# ESP32-ADC.net
KiCad netlist of a schematic drawn in EAGLE
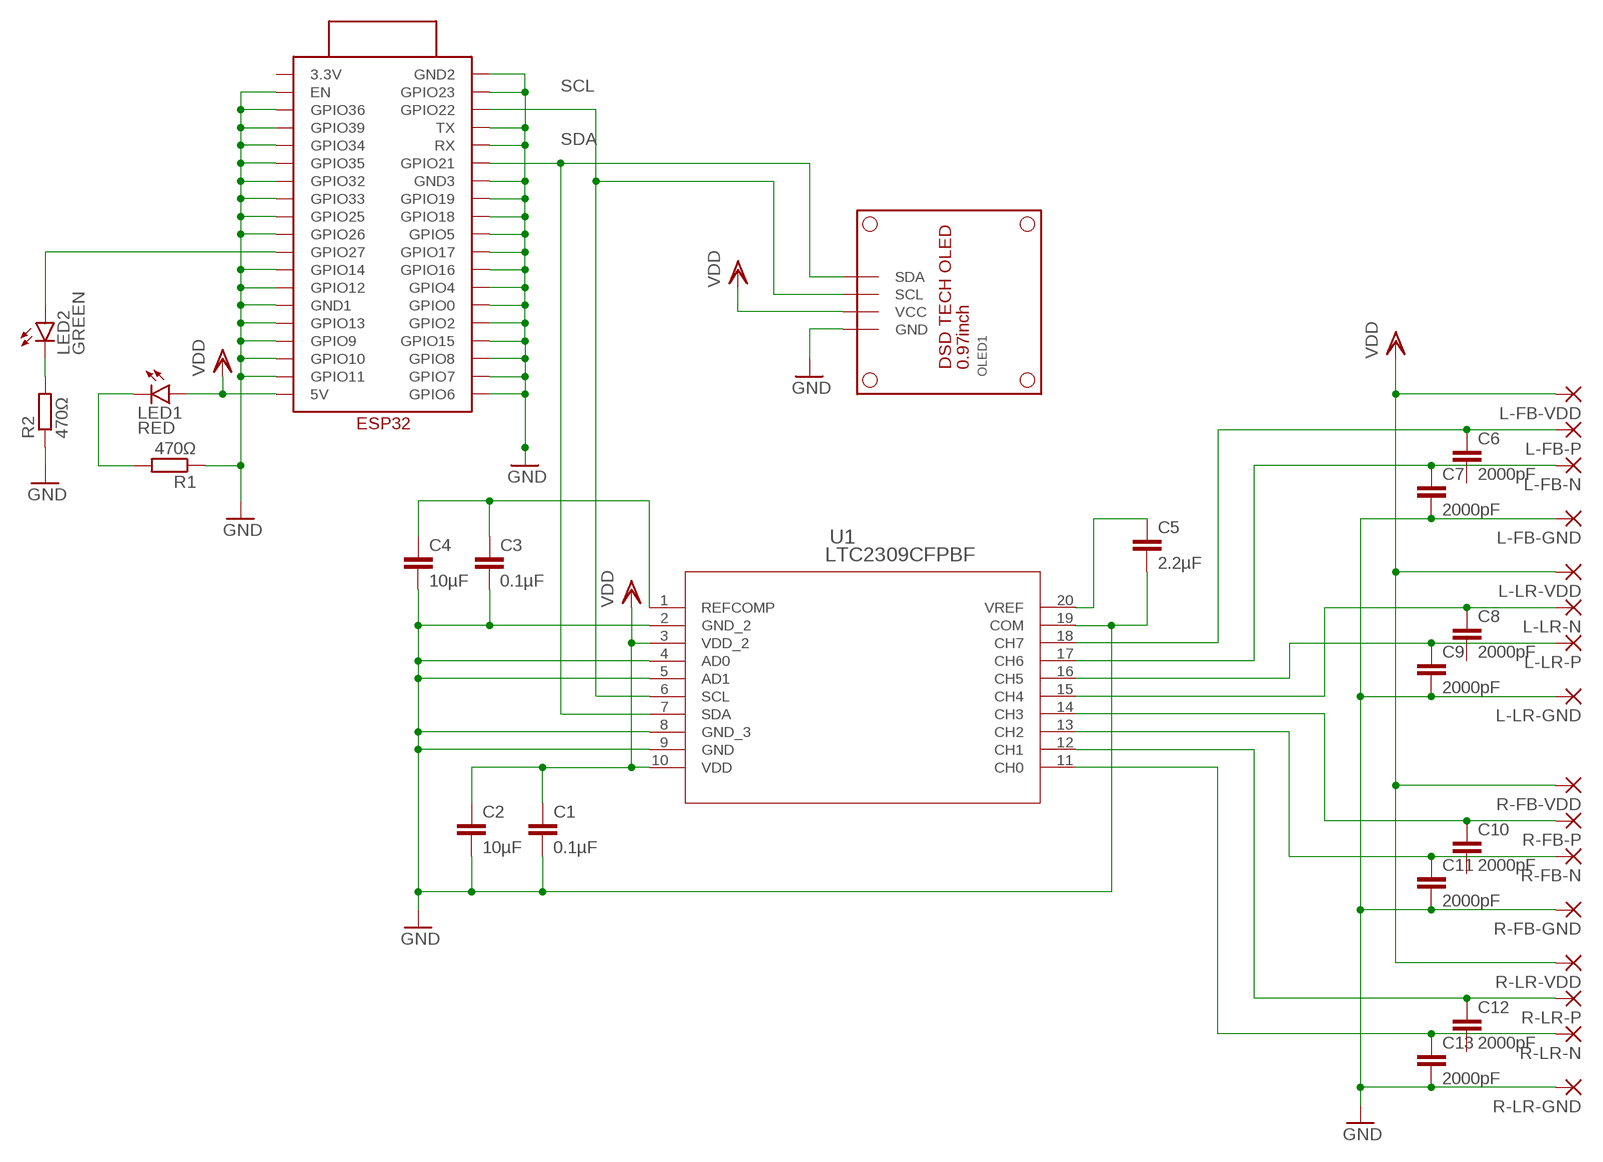
[diagram p0: schematic, sheet 1]

(export (version "E")
  (design (tool "Eeschema 10.0.6"))
  (components
    (comp (ref "C1")
      (value "0.1µF")
      (footprint "eagle-import:C3216")
      (libsource (lib "eagle-import") (part "C-EUC3216"))
    )
    (comp (ref "C2")
      (value "10µF")
      (footprint "eagle-import:C3216")
      (libsource (lib "eagle-import") (part "C-EUC3216"))
    )
    (comp (ref "C3")
      (value "0.1µF")
      (footprint "eagle-import:C3216")
      (libsource (lib "eagle-import") (part "C-EUC3216"))
    )
    (comp (ref "C4")
      (value "10µF")
      (footprint "eagle-import:C3216")
      (libsource (lib "eagle-import") (part "C-EUC3216"))
    )
    (comp (ref "C5")
      (value "2.2µF")
      (footprint "eagle-import:C3216")
      (libsource (lib "eagle-import") (part "C-EUC3216"))
    )
    (comp (ref "C6")
      (value "2000pF")
      (footprint "eagle-import:C3216")
      (libsource (lib "eagle-import") (part "C-EUC3216"))
    )
    (comp (ref "C7")
      (value "2000pF")
      (footprint "eagle-import:C3216")
      (libsource (lib "eagle-import") (part "C-EUC3216"))
    )
    (comp (ref "C8")
      (value "2000pF")
      (footprint "eagle-import:C3216")
      (libsource (lib "eagle-import") (part "C-EUC3216"))
    )
    (comp (ref "C9")
      (value "2000pF")
      (footprint "eagle-import:C3216")
      (libsource (lib "eagle-import") (part "C-EUC3216"))
    )
    (comp (ref "C10")
      (value "2000pF")
      (footprint "eagle-import:C3216")
      (libsource (lib "eagle-import") (part "C-EUC3216"))
    )
    (comp (ref "C11")
      (value "2000pF")
      (footprint "eagle-import:C3216")
      (libsource (lib "eagle-import") (part "C-EUC3216"))
    )
    (comp (ref "C12")
      (value "2000pF")
      (footprint "eagle-import:C3216")
      (libsource (lib "eagle-import") (part "C-EUC3216"))
    )
    (comp (ref "C13")
      (value "2000pF")
      (footprint "eagle-import:C3216")
      (libsource (lib "eagle-import") (part "C-EUC3216"))
    )
    (comp (ref "L-FB-GND")
      (value "SMD2")
      (footprint "eagle-import:SMD1,27-2,54")
      (libsource (lib "eagle-import") (part "SMD2"))
    )
    (comp (ref "L-FB-N")
      (value "SMD2")
      (footprint "eagle-import:SMD1,27-2,54")
      (libsource (lib "eagle-import") (part "SMD2"))
    )
    (comp (ref "L-FB-P")
      (value "SMD2")
      (footprint "eagle-import:SMD1,27-2,54")
      (libsource (lib "eagle-import") (part "SMD2"))
    )
    (comp (ref "L-FB-VDD")
      (value "SMD2")
      (footprint "eagle-import:SMD1,27-2,54")
      (libsource (lib "eagle-import") (part "SMD2"))
    )
    (comp (ref "L-LR-GND")
      (value "SMD2")
      (footprint "eagle-import:SMD1,27-2,54")
      (libsource (lib "eagle-import") (part "SMD2"))
    )
    (comp (ref "L-LR-N")
      (value "SMD2")
      (footprint "eagle-import:SMD1,27-2,54")
      (libsource (lib "eagle-import") (part "SMD2"))
    )
    (comp (ref "L-LR-P")
      (value "SMD2")
      (footprint "eagle-import:SMD1,27-2,54")
      (libsource (lib "eagle-import") (part "SMD2"))
    )
    (comp (ref "L-LR-VDD")
      (value "SMD2")
      (footprint "eagle-import:SMD1,27-2,54")
      (libsource (lib "eagle-import") (part "SMD2"))
    )
    (comp (ref "LED1")
      (value "RED")
      (footprint "eagle-import:LED3MM")
      (libsource (lib "eagle-import") (part "LED3MM"))
    )
    (comp (ref "LED2")
      (value "GREEN")
      (footprint "eagle-import:LED3MM")
      (libsource (lib "eagle-import") (part "LED3MM"))
    )
    (comp (ref "OLED1")
      (value "DSDTECH_ARDUINO_AVRCOMPATIBLE_IIC_OLED")
      (footprint "eagle-import:DSDTECH0.96_ARDUINOAVRCOMPATIBLEIICOLEDLCDSCREENSUPPORTU8GLIB")
      (libsource (lib "eagle-import") (part "DSDTECH_ARDUINO_AVRCOMPATIBLE_IIC_OLED"))
    )
    (comp (ref "R-FB-GND")
      (value "SMD2")
      (footprint "eagle-import:SMD1,27-2,54")
      (libsource (lib "eagle-import") (part "SMD2"))
    )
    (comp (ref "R-FB-N")
      (value "SMD2")
      (footprint "eagle-import:SMD1,27-2,54")
      (libsource (lib "eagle-import") (part "SMD2"))
    )
    (comp (ref "R-FB-P")
      (value "SMD2")
      (footprint "eagle-import:SMD1,27-2,54")
      (libsource (lib "eagle-import") (part "SMD2"))
    )
    (comp (ref "R-FB-VDD")
      (value "SMD2")
      (footprint "eagle-import:SMD1,27-2,54")
      (libsource (lib "eagle-import") (part "SMD2"))
    )
    (comp (ref "R-LR-GND")
      (value "SMD2")
      (footprint "eagle-import:SMD1,27-2,54")
      (libsource (lib "eagle-import") (part "SMD2"))
    )
    (comp (ref "R-LR-N")
      (value "SMD2")
      (footprint "eagle-import:SMD1,27-2,54")
      (libsource (lib "eagle-import") (part "SMD2"))
    )
    (comp (ref "R-LR-P")
      (value "SMD2")
      (footprint "eagle-import:SMD1,27-2,54")
      (libsource (lib "eagle-import") (part "SMD2"))
    )
    (comp (ref "R-LR-VDD")
      (value "SMD2")
      (footprint "eagle-import:SMD1,27-2,54")
      (libsource (lib "eagle-import") (part "SMD2"))
    )
    (comp (ref "R1")
      (value "470Ω")
      (footprint "eagle-import:R3216W")
      (libsource (lib "eagle-import") (part "R-EU_R3216W"))
    )
    (comp (ref "R2")
      (value "470Ω")
      (footprint "eagle-import:R3216W")
      (libsource (lib "eagle-import") (part "R-EU_R3216W"))
    )
    (comp (ref "U$2")
      (value "ESP32ESP32_WIFI")
      (footprint "eagle-import:ESP32_WIFI")
      (libsource (lib "eagle-import") (part "ESP32ESP32_WIFI"))
    )
    (comp (ref "U1")
      (value "LTC2309CFPBF")
      (footprint "eagle-import:TSSOP-20_F_LIT")
      (fields
        (field (name "MANUFACTURER_PART_NUMBER") "LTC2309CF#PBF")
        (field (name "COPYRIGHT") "Copyright (C) 2021 Ultra Librarian. All rights reserved.")
      )
      (libsource (lib "eagle-import") (part "LTC2309CFPBF"))
    )
  )
  (nets
    (net (code "1") (name "/SCL") (class "Default")
      (node (ref "OLED1") (pin "SCL") (pinfunction "SCL_SCL") (pintype "bidirectional"))
      (node (ref "U$2") (pin "GPIO22") (pinfunction "GPIO22_GPIO22") (pintype "bidirectional"))
      (node (ref "U1") (pin "6") (pinfunction "SCL_6") (pintype "passive"))
    )
    (net (code "2") (name "/SDA") (class "Default")
      (node (ref "OLED1") (pin "SDA") (pinfunction "SDA_SDA") (pintype "bidirectional"))
      (node (ref "U$2") (pin "GPIO21") (pinfunction "GPIO21_GPIO21") (pintype "bidirectional"))
      (node (ref "U1") (pin "7") (pinfunction "SDA_7") (pintype "bidirectional"))
    )
    (net (code "3") (name "GND") (class "Default")
      (node (ref "C1") (pin "2") (pinfunction "2_2") (pintype "passive"))
      (node (ref "C11") (pin "2") (pinfunction "2_2") (pintype "passive"))
      (node (ref "C13") (pin "2") (pinfunction "2_2") (pintype "passive"))
      (node (ref "C2") (pin "2") (pinfunction "2_2") (pintype "passive"))
      (node (ref "C3") (pin "2") (pinfunction "2_2") (pintype "passive"))
      (node (ref "C4") (pin "2") (pinfunction "2_2") (pintype "passive"))
      (node (ref "C5") (pin "2") (pinfunction "2_2") (pintype "passive"))
      (node (ref "C7") (pin "2") (pinfunction "2_2") (pintype "passive"))
      (node (ref "C9") (pin "2") (pinfunction "2_2") (pintype "passive"))
      (node (ref "L-FB-GND") (pin "1") (pinfunction "P_1") (pintype "passive"))
      (node (ref "L-LR-GND") (pin "1") (pinfunction "P_1") (pintype "passive"))
      (node (ref "OLED1") (pin "GND") (pinfunction "GND_GND") (pintype "bidirectional"))
      (node (ref "R-FB-GND") (pin "1") (pinfunction "P_1") (pintype "passive"))
      (node (ref "R-LR-GND") (pin "1") (pinfunction "P_1") (pintype "passive"))
      (node (ref "R1") (pin "1") (pinfunction "1_1") (pintype "passive"))
      (node (ref "R2") (pin "1") (pinfunction "1_1") (pintype "passive"))
      (node (ref "U$2") (pin "EN") (pinfunction "EN_EN") (pintype "bidirectional"))
      (node (ref "U$2") (pin "GND1") (pinfunction "GND1_GND1") (pintype "bidirectional"))
      (node (ref "U$2") (pin "GND2") (pinfunction "GND2_GND2") (pintype "bidirectional"))
      (node (ref "U$2") (pin "GND3") (pinfunction "GND3_GND3") (pintype "bidirectional"))
      (node (ref "U$2") (pin "GPIO0") (pinfunction "GPIO0_GPIO0") (pintype "bidirectional"))
      (node (ref "U$2") (pin "GPIO10") (pinfunction "GPIO10_GPIO10") (pintype "bidirectional"))
      (node (ref "U$2") (pin "GPIO11") (pinfunction "GPIO11_GPIO11") (pintype "bidirectional"))
      (node (ref "U$2") (pin "GPIO12") (pinfunction "GPIO12_GPIO12") (pintype "bidirectional"))
      (node (ref "U$2") (pin "GPIO13") (pinfunction "GPIO13_GPIO13") (pintype "bidirectional"))
      (node (ref "U$2") (pin "GPIO14") (pinfunction "GPIO14_GPIO14") (pintype "bidirectional"))
      (node (ref "U$2") (pin "GPIO15") (pinfunction "GPIO15_GPIO15") (pintype "bidirectional"))
      (node (ref "U$2") (pin "GPIO16") (pinfunction "GPIO16_GPIO16") (pintype "bidirectional"))
      (node (ref "U$2") (pin "GPIO17") (pinfunction "GPIO17_GPIO17") (pintype "bidirectional"))
      (node (ref "U$2") (pin "GPIO18") (pinfunction "GPIO18_GPIO18") (pintype "bidirectional"))
      (node (ref "U$2") (pin "GPIO19") (pinfunction "GPIO19_GPIO19") (pintype "bidirectional"))
      (node (ref "U$2") (pin "GPIO2") (pinfunction "GPIO2_GPIO2") (pintype "bidirectional"))
      (node (ref "U$2") (pin "GPIO23") (pinfunction "GPIO23_GPIO23") (pintype "bidirectional"))
      (node (ref "U$2") (pin "GPIO25") (pinfunction "GPIO25_GPIO25") (pintype "bidirectional"))
      (node (ref "U$2") (pin "GPIO26") (pinfunction "GPIO26_GPIO26") (pintype "bidirectional"))
      (node (ref "U$2") (pin "GPIO32") (pinfunction "GPIO32_GPIO32") (pintype "bidirectional"))
      (node (ref "U$2") (pin "GPIO33") (pinfunction "GPIO33_GPIO33") (pintype "bidirectional"))
      (node (ref "U$2") (pin "GPIO34") (pinfunction "GPIO34_GPIO34") (pintype "bidirectional"))
      (node (ref "U$2") (pin "GPIO35") (pinfunction "GPIO35_GPIO35") (pintype "bidirectional"))
      (node (ref "U$2") (pin "GPIO36") (pinfunction "GPIO36_GPIO36") (pintype "bidirectional"))
      (node (ref "U$2") (pin "GPIO39") (pinfunction "GPIO39_GPIO39") (pintype "bidirectional"))
      (node (ref "U$2") (pin "GPIO4") (pinfunction "GPIO4_GPIO4") (pintype "bidirectional"))
      (node (ref "U$2") (pin "GPIO5") (pinfunction "GPIO5_GPIO5") (pintype "bidirectional"))
      (node (ref "U$2") (pin "GPIO6") (pinfunction "GPIO6_GPIO6") (pintype "bidirectional"))
      (node (ref "U$2") (pin "GPIO7") (pinfunction "GPIO7_GPIO7") (pintype "bidirectional"))
      (node (ref "U$2") (pin "GPIO8") (pinfunction "GPIO8_GPIO8") (pintype "bidirectional"))
      (node (ref "U$2") (pin "GPIO9") (pinfunction "GPIO9_GPIO9") (pintype "bidirectional"))
      (node (ref "U$2") (pin "RX") (pinfunction "RX_RX") (pintype "bidirectional"))
      (node (ref "U$2") (pin "TX") (pinfunction "TX_TX") (pintype "bidirectional"))
      (node (ref "U1") (pin "19") (pinfunction "COM_19") (pintype "input"))
      (node (ref "U1") (pin "2") (pinfunction "GND_2_2") (pintype "power_in"))
      (node (ref "U1") (pin "4") (pinfunction "AD0_4") (pintype "passive"))
      (node (ref "U1") (pin "5") (pinfunction "AD1_5") (pintype "passive"))
      (node (ref "U1") (pin "8") (pinfunction "GND_3_8") (pintype "power_in"))
      (node (ref "U1") (pin "9") (pinfunction "GND_9") (pintype "power_in"))
    )
    (net (code "4") (name "Net-(L-FB-N-P)") (class "Default")
      (node (ref "C7") (pin "1") (pinfunction "1_1") (pintype "passive"))
      (node (ref "L-FB-N") (pin "1") (pinfunction "P_1") (pintype "passive"))
      (node (ref "U1") (pin "17") (pinfunction "CH6_17") (pintype "input"))
    )
    (net (code "5") (name "Net-(L-FB-P-P)") (class "Default")
      (node (ref "C6") (pin "1") (pinfunction "1_1") (pintype "passive"))
      (node (ref "L-FB-P") (pin "1") (pinfunction "P_1") (pintype "passive"))
      (node (ref "U1") (pin "18") (pinfunction "CH7_18") (pintype "input"))
    )
    (net (code "6") (name "Net-(L-LR-N-P)") (class "Default")
      (node (ref "C8") (pin "1") (pinfunction "1_1") (pintype "passive"))
      (node (ref "L-LR-N") (pin "1") (pinfunction "P_1") (pintype "passive"))
      (node (ref "U1") (pin "15") (pinfunction "CH4_15") (pintype "input"))
    )
    (net (code "7") (name "Net-(L-LR-P-P)") (class "Default")
      (node (ref "C9") (pin "1") (pinfunction "1_1") (pintype "passive"))
      (node (ref "L-LR-P") (pin "1") (pinfunction "P_1") (pintype "passive"))
      (node (ref "U1") (pin "16") (pinfunction "CH5_16") (pintype "input"))
    )
    (net (code "8") (name "Net-(LED1-C)") (class "Default")
      (node (ref "LED1") (pin "K") (pinfunction "C_K") (pintype "passive"))
      (node (ref "R1") (pin "2") (pinfunction "2_2") (pintype "passive"))
    )
    (net (code "9") (name "Net-(LED2-C)") (class "Default")
      (node (ref "LED2") (pin "K") (pinfunction "C_K") (pintype "passive"))
      (node (ref "R2") (pin "2") (pinfunction "2_2") (pintype "passive"))
    )
    (net (code "10") (name "Net-(LED2-PadA)") (class "Default")
      (node (ref "LED2") (pin "A") (pinfunction "A_A") (pintype "passive"))
      (node (ref "U$2") (pin "GPIO27") (pinfunction "GPIO27_GPIO27") (pintype "bidirectional"))
    )
    (net (code "11") (name "Net-(R-FB-N-P)") (class "Default")
      (node (ref "C11") (pin "1") (pinfunction "1_1") (pintype "passive"))
      (node (ref "R-FB-N") (pin "1") (pinfunction "P_1") (pintype "passive"))
      (node (ref "U1") (pin "13") (pinfunction "CH2_13") (pintype "input"))
    )
    (net (code "12") (name "Net-(R-FB-P-P)") (class "Default")
      (node (ref "C10") (pin "1") (pinfunction "1_1") (pintype "passive"))
      (node (ref "R-FB-P") (pin "1") (pinfunction "P_1") (pintype "passive"))
      (node (ref "U1") (pin "14") (pinfunction "CH3_14") (pintype "input"))
    )
    (net (code "13") (name "Net-(R-LR-N-P)") (class "Default")
      (node (ref "C13") (pin "1") (pinfunction "1_1") (pintype "passive"))
      (node (ref "R-LR-N") (pin "1") (pinfunction "P_1") (pintype "passive"))
      (node (ref "U1") (pin "11") (pinfunction "CH0_11") (pintype "input"))
    )
    (net (code "14") (name "Net-(R-LR-P-P)") (class "Default")
      (node (ref "C12") (pin "1") (pinfunction "1_1") (pintype "passive"))
      (node (ref "R-LR-P") (pin "1") (pinfunction "P_1") (pintype "passive"))
      (node (ref "U1") (pin "12") (pinfunction "CH1_12") (pintype "input"))
    )
    (net (code "15") (name "Net-(U1-REFCOMP)") (class "Default")
      (node (ref "C3") (pin "1") (pinfunction "1_1") (pintype "passive"))
      (node (ref "C4") (pin "1") (pinfunction "1_1") (pintype "passive"))
      (node (ref "U1") (pin "1") (pinfunction "REFCOMP_1") (pintype "output"))
    )
    (net (code "16") (name "Net-(U1-VREF)") (class "Default")
      (node (ref "C5") (pin "1") (pinfunction "1_1") (pintype "passive"))
      (node (ref "U1") (pin "20") (pinfunction "VREF_20") (pintype "output"))
    )
    (net (code "17") (name "VDD") (class "Default")
      (node (ref "C1") (pin "1") (pinfunction "1_1") (pintype "passive"))
      (node (ref "C2") (pin "1") (pinfunction "1_1") (pintype "passive"))
      (node (ref "L-FB-VDD") (pin "1") (pinfunction "P_1") (pintype "passive"))
      (node (ref "L-LR-VDD") (pin "1") (pinfunction "P_1") (pintype "passive"))
      (node (ref "LED1") (pin "A") (pinfunction "A_A") (pintype "passive"))
      (node (ref "OLED1") (pin "VCC") (pinfunction "VCC_VCC") (pintype "bidirectional"))
      (node (ref "R-FB-VDD") (pin "1") (pinfunction "P_1") (pintype "passive"))
      (node (ref "R-LR-VDD") (pin "1") (pinfunction "P_1") (pintype "passive"))
      (node (ref "U$2") (pin "5V") (pinfunction "5V_5V") (pintype "bidirectional"))
      (node (ref "U1") (pin "10") (pinfunction "VDD_10") (pintype "power_in"))
      (node (ref "U1") (pin "3") (pinfunction "VDD_2_3") (pintype "power_in"))
    )
    (net (code "18") (name "unconnected-(C6-Pad2)") (class "Default")
      (node (ref "C6") (pin "2") (pinfunction "2_2") (pintype "passive"))
    )
    (net (code "19") (name "unconnected-(C8-Pad2)") (class "Default")
      (node (ref "C8") (pin "2") (pinfunction "2_2") (pintype "passive"))
    )
    (net (code "20") (name "unconnected-(C10-Pad2)") (class "Default")
      (node (ref "C10") (pin "2") (pinfunction "2_2") (pintype "passive"))
    )
    (net (code "21") (name "unconnected-(C12-Pad2)") (class "Default")
      (node (ref "C12") (pin "2") (pinfunction "2_2") (pintype "passive"))
    )
    (net (code "22") (name "unconnected-(U$2-Pad3.3V)") (class "Default")
      (node (ref "U$2") (pin "3.3V") (pinfunction "3.3V_3.3V") (pintype "bidirectional"))
    )
  )
)
